# IMU.net
KiCad netlist of a schematic drawn in Altium Designer
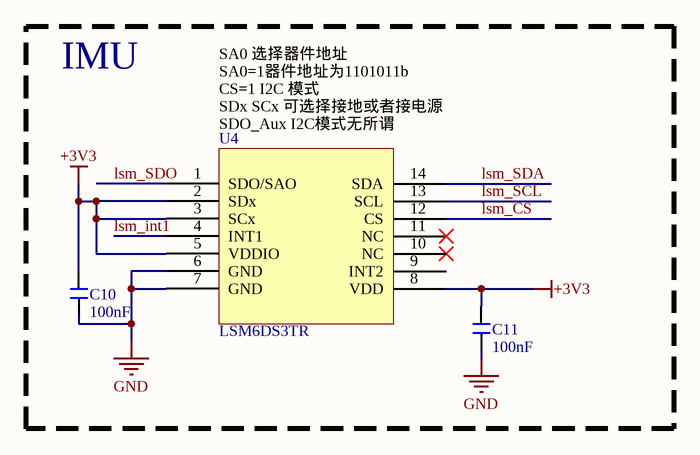
[diagram p0: IMU.SchDoc]

(export (version "E")
  (design (tool "Eeschema 10.0.6"))
  (components
    (comp (ref "C10")
      (value "100nF")
      (footprint "C 0201_L")
      (description "贴片电容")
      (libsource (lib "0.1 - 电阻-电容-电感") (part "C"))
    )
    (comp (ref "C11")
      (value "100nF")
      (footprint "C 0201_L")
      (description "贴片电容")
      (libsource (lib "0.1 - 电阻-电容-电感") (part "C"))
    )
    (comp (ref "U4") (value "LSM6DS3TR") (footprint "LAG-14") (libsource (lib "rhd2216") (part "LSM6DS3TR")))
  )
  (nets
    (net (code "1") (name "+3V3") (class "Default")
      (node (ref "C10") (pin "2") (pinfunction "2_2") (pintype "passive"))
      (node (ref "C11") (pin "2") (pinfunction "2_2") (pintype "passive"))
      (node (ref "U4") (pin "2") (pinfunction "SDx_2") (pintype "passive"))
      (node (ref "U4") (pin "3") (pinfunction "SCx_3") (pintype "passive"))
      (node (ref "U4") (pin "5") (pinfunction "VDDIO_5") (pintype "passive"))
      (node (ref "U4") (pin "8") (pinfunction "VDD_8") (pintype "passive"))
    )
    (net (code "2") (name "/lsm_CS") (class "Default")
      (node (ref "U4") (pin "12") (pinfunction "CS_12") (pintype "passive"))
    )
    (net (code "3") (name "/lsm_SCL") (class "Default")
      (node (ref "U4") (pin "13") (pinfunction "SCL_13") (pintype "passive"))
    )
    (net (code "4") (name "/lsm_SDA") (class "Default")
      (node (ref "U4") (pin "14") (pinfunction "SDA_14") (pintype "passive"))
    )
    (net (code "5") (name "/lsm_SDO") (class "Default")
      (node (ref "U4") (pin "1") (pinfunction "SDO/SAO_1") (pintype "passive"))
    )
    (net (code "6") (name "/lsm_int1") (class "Default")
      (node (ref "U4") (pin "4") (pinfunction "INT1_4") (pintype "passive"))
    )
    (net (code "7") (name "GND") (class "Default")
      (node (ref "C10") (pin "1") (pinfunction "1_1") (pintype "passive"))
      (node (ref "C11") (pin "1") (pinfunction "1_1") (pintype "passive"))
      (node (ref "U4") (pin "6") (pinfunction "GND_6") (pintype "passive"))
      (node (ref "U4") (pin "7") (pinfunction "GND_7") (pintype "passive"))
    )
    (net (code "8") (name "unconnected-(U4-INT2-Pad9)") (class "Default")
      (node (ref "U4") (pin "9") (pinfunction "INT2_9") (pintype "passive"))
    )
    (net (code "9") (name "unconnected-(U4-NC-Pad10)") (class "Default")
      (node (ref "U4") (pin "10") (pinfunction "NC_10") (pintype "passive+no_connect"))
    )
    (net (code "10") (name "unconnected-(U4-NC-Pad11)") (class "Default")
      (node (ref "U4") (pin "11") (pinfunction "NC_11") (pintype "passive+no_connect"))
    )
  )
)
